# Openbook_Schematic.net
KiCad netlist of a schematic drawn in EAGLE
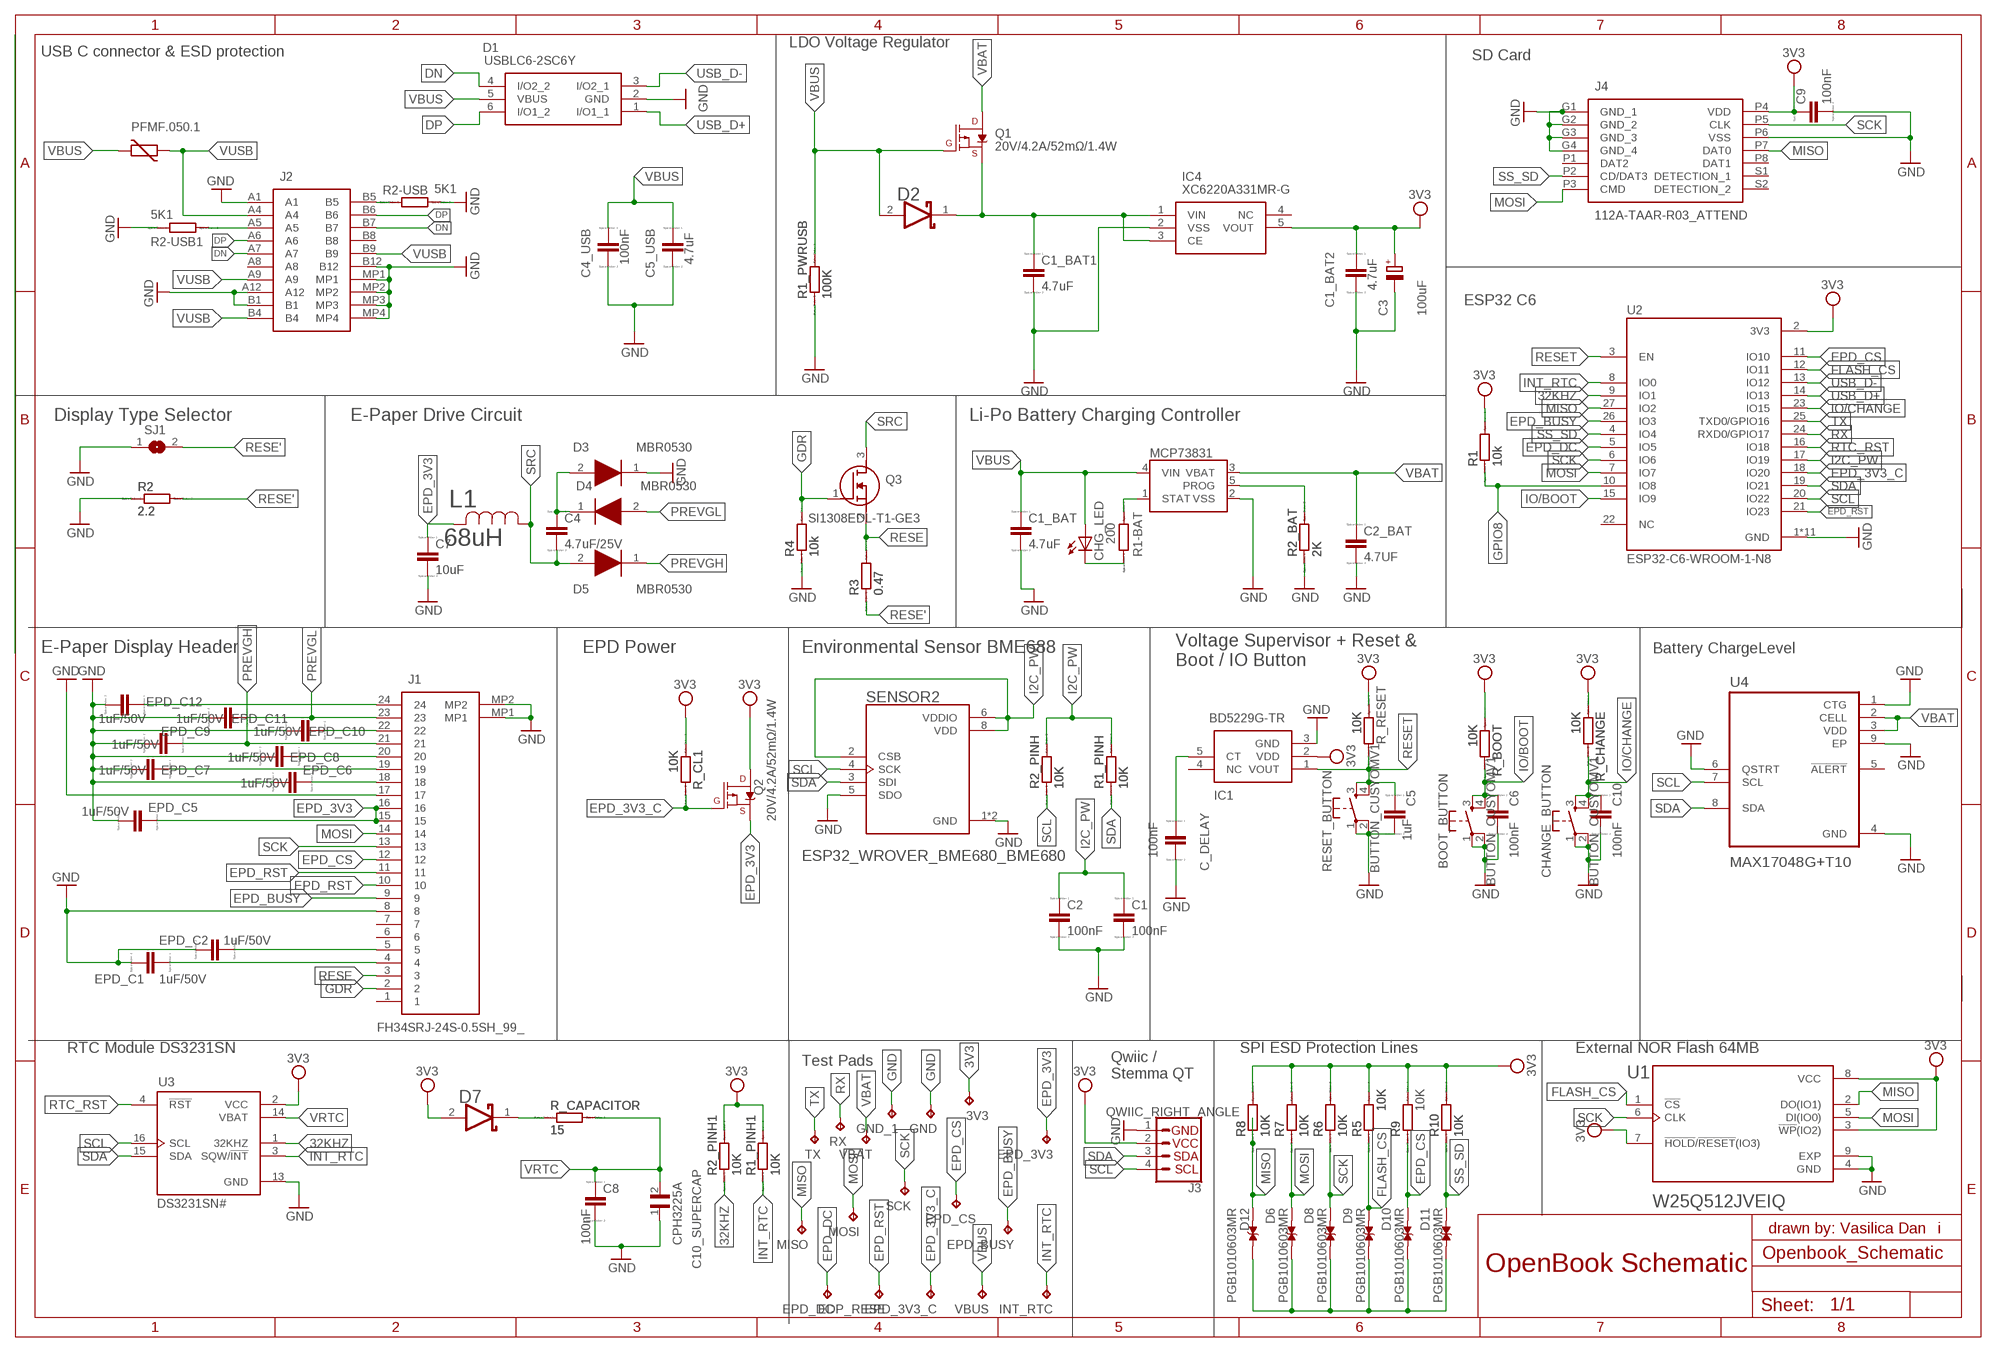
[diagram p0: schematic, sheet 1]

(export (version "E")
  (design (tool "Eeschema 10.0.6"))
  (components
    (comp (ref "3V3")
      (value "TPTP20R")
      (footprint "eagle-import:TP20R")
      (libsource (lib "eagle-import") (part "TPTP20R"))
    )
    (comp (ref "BOOT_BUTTON")
      (value "BUTTON_CUSYOMV1")
      (footprint "eagle-import:MYBUTTON")
      (libsource (lib "eagle-import") (part "BUTTON_CUSYOMV1"))
    )
    (comp (ref "C1")
      (value "100nF")
      (footprint "eagle-import:ESP32_WROVER_EAGLE-LTSPICE_C0402")
      (libsource (lib "eagle-import") (part "ESP32_WROVER_EAGLE-LTSPICE_CC0402"))
    )
    (comp (ref "C1_BAT")
      (value "4.7uF")
      (footprint "eagle-import:ESP32_WROVER_EAGLE-LTSPICE_C0402")
      (libsource (lib "eagle-import") (part "ESP32_WROVER_EAGLE-LTSPICE_CC0402"))
    )
    (comp (ref "C1_BAT1")
      (value "4.7uF")
      (footprint "eagle-import:ESP32_WROVER_EAGLE-LTSPICE_C0402")
      (libsource (lib "eagle-import") (part "ESP32_WROVER_EAGLE-LTSPICE_CC0402"))
    )
    (comp (ref "C1_BAT2")
      (value "4.7uF")
      (footprint "eagle-import:ESP32_WROVER_EAGLE-LTSPICE_C0402")
      (libsource (lib "eagle-import") (part "ESP32_WROVER_EAGLE-LTSPICE_CC0402"))
    )
    (comp (ref "C2")
      (value "100nF")
      (footprint "eagle-import:ESP32_WROVER_EAGLE-LTSPICE_C0402")
      (libsource (lib "eagle-import") (part "ESP32_WROVER_EAGLE-LTSPICE_CC0402"))
    )
    (comp (ref "C2_BAT")
      (value "4.7UF")
      (footprint "eagle-import:ESP32_WROVER_EAGLE-LTSPICE_C0402")
      (libsource (lib "eagle-import") (part "ESP32_WROVER_EAGLE-LTSPICE_CC0402"))
    )
    (comp (ref "C3")
      (value "100uF")
      (footprint "eagle-import:RCL_CT3528")
      (libsource (lib "eagle-import") (part "RCL_CPOL-EUCT3528"))
    )
    (comp (ref "C4")
      (value "4.7uF/25V")
      (footprint "eagle-import:ESP32_WROVER_EAGLE-LTSPICE_C0402")
      (libsource (lib "eagle-import") (part "ESP32_WROVER_EAGLE-LTSPICE_CC0402"))
    )
    (comp (ref "C4_USB")
      (value "100nF")
      (footprint "eagle-import:ESP32_WROVER_EAGLE-LTSPICE_C0402")
      (libsource (lib "eagle-import") (part "ESP32_WROVER_EAGLE-LTSPICE_CC0402"))
    )
    (comp (ref "C5")
      (value "1uF")
      (footprint "eagle-import:ESP32_WROVER_EAGLE-LTSPICE_C0402")
      (libsource (lib "eagle-import") (part "ESP32_WROVER_EAGLE-LTSPICE_CC0402"))
    )
    (comp (ref "C5_USB")
      (value "4.7uF")
      (footprint "eagle-import:ESP32_WROVER_EAGLE-LTSPICE_C0402")
      (libsource (lib "eagle-import") (part "ESP32_WROVER_EAGLE-LTSPICE_CC0402"))
    )
    (comp (ref "C6")
      (value "100nF")
      (footprint "eagle-import:ESP32_WROVER_EAGLE-LTSPICE_C0402")
      (libsource (lib "eagle-import") (part "ESP32_WROVER_EAGLE-LTSPICE_CC0402"))
    )
    (comp (ref "C7")
      (value "10uF")
      (footprint "eagle-import:ESP32_WROVER_EAGLE-LTSPICE_C0402")
      (libsource (lib "eagle-import") (part "ESP32_WROVER_EAGLE-LTSPICE_CC0402"))
    )
    (comp (ref "C8")
      (value "100nF")
      (footprint "eagle-import:ESP32_WROVER_EAGLE-LTSPICE_C0402")
      (libsource (lib "eagle-import") (part "ESP32_WROVER_EAGLE-LTSPICE_CC0402"))
    )
    (comp (ref "C9")
      (value "100nF")
      (footprint "eagle-import:ESP32_WROVER_EAGLE-LTSPICE_C0402")
      (libsource (lib "eagle-import") (part "ESP32_WROVER_EAGLE-LTSPICE_CC0402"))
    )
    (comp (ref "C10")
      (value "100nF")
      (footprint "eagle-import:ESP32_WROVER_EAGLE-LTSPICE_C0402")
      (libsource (lib "eagle-import") (part "ESP32_WROVER_EAGLE-LTSPICE_CC0402"))
    )
    (comp (ref "C10_SUPERCAP")
      (value "CPH3225A")
      (footprint "eagle-import:CAPCP3225X100N")
      (fields (field (name "MF") "Seiko Instruments"))
      (libsource (lib "eagle-import") (part "CPH3225A"))
    )
    (comp (ref "CHANGE_BUTTON")
      (value "BUTTON_CUSYOMV1")
      (footprint "eagle-import:MYBUTTON")
      (libsource (lib "eagle-import") (part "BUTTON_CUSYOMV1"))
    )
    (comp (ref "CHG_LED")
      (value "ADAFRUIT_LEDCHIP-LED0603")
      (footprint "eagle-import:ADAFRUIT_CHIP-LED0603")
      (libsource (lib "eagle-import") (part "ADAFRUIT_LEDCHIP-LED0603"))
    )
    (comp (ref "C_DELAY")
      (value "100nF")
      (footprint "eagle-import:ESP32_WROVER_EAGLE-LTSPICE_C0402")
      (libsource (lib "eagle-import") (part "ESP32_WROVER_EAGLE-LTSPICE_CC0402"))
    )
    (comp (ref "D1")
      (value "USBLC6-2SC6Y")
      (footprint "eagle-import:SOT95P280X145-6N")
      (fields (field (name "MF") "STMicroelectronics"))
      (libsource (lib "eagle-import") (part "USBLC6-2SC6Y"))
    )
    (comp (ref "D2")
      (value "ESP32_WROVER_AVX---SD0805S020S1R0_AVX_SD0805S020S1R0_0_0AVX_SD0805S020S1R0_0_0")
      (footprint "eagle-import:ESP32_WROVER_AVX---SD0805S020S1R0_AVX_SD0805S020S1R0_0")
      (fields
        (field (name "DIGIKEY_PART_NUMBER") "478-7800-1-ND")
        (field (name "MF") "AVX")
        (field (name "MOUSER_PART_NUMBER") "581-SD0805S020S1R0")
      )
      (libsource (lib "eagle-import") (part "ESP32_WROVER_AVX---SD0805S020S1R0_AVX_SD0805S020S1R0_0_0AVX_SD0805S020S1R0_0_0"))
    )
    (comp (ref "D3")
      (value "MBR0530")
      (footprint "eagle-import:SOD3716X135N")
      (fields (field (name "MF") "ON Semiconductor"))
      (libsource (lib "eagle-import") (part "MBR0530"))
    )
    (comp (ref "D4")
      (value "MBR0530")
      (footprint "eagle-import:SOD3716X135N")
      (fields (field (name "MF") "ON Semiconductor"))
      (libsource (lib "eagle-import") (part "MBR0530"))
    )
    (comp (ref "D5")
      (value "MBR0530")
      (footprint "eagle-import:SOD3716X135N")
      (fields (field (name "MF") "ON Semiconductor"))
      (libsource (lib "eagle-import") (part "MBR0530"))
    )
    (comp (ref "D6")
      (value "PGB1010603MR")
      (footprint "eagle-import:DIOC1608X36N")
      (fields (field (name "MF") "Littelfuse Inc."))
      (libsource (lib "eagle-import") (part "PGB1010603MR"))
    )
    (comp (ref "D7")
      (value "ESP32_WROVER_AVX---SD0805S020S1R0_AVX_SD0805S020S1R0_0_0AVX_SD0805S020S1R0_0_0")
      (footprint "eagle-import:ESP32_WROVER_AVX---SD0805S020S1R0_AVX_SD0805S020S1R0_0")
      (fields
        (field (name "DIGIKEY_PART_NUMBER") "478-7800-1-ND")
        (field (name "MF") "AVX")
        (field (name "MOUSER_PART_NUMBER") "581-SD0805S020S1R0")
      )
      (libsource (lib "eagle-import") (part "ESP32_WROVER_AVX---SD0805S020S1R0_AVX_SD0805S020S1R0_0_0AVX_SD0805S020S1R0_0_0"))
    )
    (comp (ref "D8")
      (value "PGB1010603MR")
      (footprint "eagle-import:DIOC1608X36N")
      (fields (field (name "MF") "Littelfuse Inc."))
      (libsource (lib "eagle-import") (part "PGB1010603MR"))
    )
    (comp (ref "D9")
      (value "PGB1010603MR")
      (footprint "eagle-import:DIOC1608X36N")
      (fields (field (name "MF") "Littelfuse Inc."))
      (libsource (lib "eagle-import") (part "PGB1010603MR"))
    )
    (comp (ref "D10")
      (value "PGB1010603MR")
      (footprint "eagle-import:DIOC1608X36N")
      (fields (field (name "MF") "Littelfuse Inc."))
      (libsource (lib "eagle-import") (part "PGB1010603MR"))
    )
    (comp (ref "D11")
      (value "PGB1010603MR")
      (footprint "eagle-import:DIOC1608X36N")
      (fields (field (name "MF") "Littelfuse Inc."))
      (libsource (lib "eagle-import") (part "PGB1010603MR"))
    )
    (comp (ref "D12")
      (value "PGB1010603MR")
      (footprint "eagle-import:DIOC1608X36N")
      (fields (field (name "MF") "Littelfuse Inc."))
      (libsource (lib "eagle-import") (part "PGB1010603MR"))
    )
    (comp (ref "EDP_RESE")
      (value "TPTP20R")
      (footprint "eagle-import:TP20R")
      (libsource (lib "eagle-import") (part "TPTP20R"))
    )
    (comp (ref "EPD_3V3")
      (value "TPTP20R")
      (footprint "eagle-import:TP20R")
      (libsource (lib "eagle-import") (part "TPTP20R"))
    )
    (comp (ref "EPD_3V3_C")
      (value "TPTP20R")
      (footprint "eagle-import:TP20R")
      (libsource (lib "eagle-import") (part "TPTP20R"))
    )
    (comp (ref "EPD_BUSY")
      (value "TPTP20R")
      (footprint "eagle-import:TP20R")
      (libsource (lib "eagle-import") (part "TPTP20R"))
    )
    (comp (ref "EPD_C1")
      (value "1uF/50V")
      (footprint "eagle-import:ESP32_WROVER_EAGLE-LTSPICE_C0402")
      (libsource (lib "eagle-import") (part "ESP32_WROVER_EAGLE-LTSPICE_CC0402"))
    )
    (comp (ref "EPD_C2")
      (value "1uF/50V")
      (footprint "eagle-import:ESP32_WROVER_EAGLE-LTSPICE_C0402")
      (libsource (lib "eagle-import") (part "ESP32_WROVER_EAGLE-LTSPICE_CC0402"))
    )
    (comp (ref "EPD_C5")
      (value "1uF/50V")
      (footprint "eagle-import:ESP32_WROVER_EAGLE-LTSPICE_C0402")
      (libsource (lib "eagle-import") (part "ESP32_WROVER_EAGLE-LTSPICE_CC0402"))
    )
    (comp (ref "EPD_C6")
      (value "1uF/50V")
      (footprint "eagle-import:ESP32_WROVER_EAGLE-LTSPICE_C0402")
      (libsource (lib "eagle-import") (part "ESP32_WROVER_EAGLE-LTSPICE_CC0402"))
    )
    (comp (ref "EPD_C7")
      (value "1uF/50V")
      (footprint "eagle-import:ESP32_WROVER_EAGLE-LTSPICE_C0402")
      (libsource (lib "eagle-import") (part "ESP32_WROVER_EAGLE-LTSPICE_CC0402"))
    )
    (comp (ref "EPD_C8")
      (value "1uF/50V")
      (footprint "eagle-import:ESP32_WROVER_EAGLE-LTSPICE_C0402")
      (libsource (lib "eagle-import") (part "ESP32_WROVER_EAGLE-LTSPICE_CC0402"))
    )
    (comp (ref "EPD_C9")
      (value "1uF/50V")
      (footprint "eagle-import:ESP32_WROVER_EAGLE-LTSPICE_C0402")
      (libsource (lib "eagle-import") (part "ESP32_WROVER_EAGLE-LTSPICE_CC0402"))
    )
    (comp (ref "EPD_C10")
      (value "1uF/50V")
      (footprint "eagle-import:ESP32_WROVER_EAGLE-LTSPICE_C0402")
      (libsource (lib "eagle-import") (part "ESP32_WROVER_EAGLE-LTSPICE_CC0402"))
    )
    (comp (ref "EPD_C11")
      (value "1uF/50V")
      (footprint "eagle-import:ESP32_WROVER_EAGLE-LTSPICE_C0402")
      (libsource (lib "eagle-import") (part "ESP32_WROVER_EAGLE-LTSPICE_CC0402"))
    )
    (comp (ref "EPD_C12")
      (value "1uF/50V")
      (footprint "eagle-import:ESP32_WROVER_EAGLE-LTSPICE_C0402")
      (libsource (lib "eagle-import") (part "ESP32_WROVER_EAGLE-LTSPICE_CC0402"))
    )
    (comp (ref "EPD_CS")
      (value "TPTP20R")
      (footprint "eagle-import:TP20R")
      (libsource (lib "eagle-import") (part "TPTP20R"))
    )
    (comp (ref "EPD_DC")
      (value "TPTP20R")
      (footprint "eagle-import:TP20R")
      (libsource (lib "eagle-import") (part "TPTP20R"))
    )
    (comp (ref "GND")
      (value "TPTP20R")
      (footprint "eagle-import:TP20R")
      (libsource (lib "eagle-import") (part "TPTP20R"))
    )
    (comp (ref "GND_1")
      (value "TPTP20R")
      (footprint "eagle-import:TP20R")
      (libsource (lib "eagle-import") (part "TPTP20R"))
    )
    (comp (ref "IC1")
      (value "BD5229G-TR")
      (footprint "eagle-import:SOT95P280X120-5N")
      (fields (field (name "MOUSER_PART_NUMBER") "755-BD5229G-TR"))
      (libsource (lib "eagle-import") (part "BD5229G-TR"))
    )
    (comp (ref "IC4")
      (value "XC6220A331MR-G")
      (footprint "eagle-import:SOT95P280X120-5N")
      (fields (field (name "MOUSER_PART_NUMBER") "865-XC6220A331MR-G"))
      (libsource (lib "eagle-import") (part "XC6220A331MR-G"))
    )
    (comp (ref "INT_RTC")
      (value "TPTP20R")
      (footprint "eagle-import:TP20R")
      (libsource (lib "eagle-import") (part "TPTP20R"))
    )
    (comp (ref "J1")
      (value "FH34SRJ-24S-0.5SH_99_")
      (footprint "eagle-import:FH34SRJ24S05SH99")
      (fields
        (field (name "MANUFACTURER_PART_NUMBER") "FH34SRJ-24S-0.5SH(99)")
        (field (name "MOUSER_PART_NUMBER") "798-FH34SRJ24S05SH99")
      )
      (libsource (lib "eagle-import") (part "FH34SRJ-24S-0.5SH_99_"))
    )
    (comp (ref "J2")
      (value "SAMACSYS_PARTS_USB4110-GF-A")
      (footprint "eagle-import:SAMACSYS_PARTS_USB4110GFA")
      (fields
        (field (name "MANUFACTURER_PART_NUMBER") "USB4110-GF-A")
        (field (name "MOUSER_PART_NUMBER") "640-USB4110-GF-A")
      )
      (libsource (lib "eagle-import") (part "SAMACSYS_PARTS_USB4110-GF-A"))
    )
    (comp (ref "J3")
      (value "QWIIC_RIGHT_ANGLE")
      (footprint "eagle-import:JST04_1MM_RA")
      (libsource (lib "eagle-import") (part "QWIIC_CONNECTORJS-1MM"))
    )
    (comp (ref "J4")
      (value "112A-TAAR-R03_ATTEND")
      (footprint "eagle-import:112ATAARR03ATTEND")
      (fields (field (name "MANUFACTURER_PART_NUMBER") "112A-TAAR-R03 ATTEND"))
      (libsource (lib "eagle-import") (part "112A-TAAR-R03_ATTEND"))
    )
    (comp (ref "L1")
      (value "68uH")
      (footprint "eagle-import:IND_4828-WE-TPC_WRE")
      (fields
        (field (name "MANUFACTURER_PART_NUMBER") "744043680")
        (field (name "COPYRIGHT") "Copyright (C) 2024 Ultra Librarian. All rights reserved.")
      )
      (libsource (lib "eagle-import") (part "744043680IND_4828-WE-TPC_WRE"))
    )
    (comp (ref "MCP73831")
      (value "ESP32_WROVER_SPARKFUN-IC-POWER_MCP73831")
      (footprint "eagle-import:ESP32_WROVER_SPARKFUN-IC-POWER_SOT23-5")
      (libsource (lib "eagle-import") (part "ESP32_WROVER_SPARKFUN-IC-POWER_MCP73831"))
    )
    (comp (ref "MISO")
      (value "TPTP20R")
      (footprint "eagle-import:TP20R")
      (libsource (lib "eagle-import") (part "TPTP20R"))
    )
    (comp (ref "MOSI")
      (value "TPTP20R")
      (footprint "eagle-import:TP20R")
      (libsource (lib "eagle-import") (part "TPTP20R"))
    )
    (comp (ref "PFMF.050.1")
      (value "ESP32C6_VARISTORCN1812")
      (footprint "eagle-import:ESP32C6_VARISTOR_CT_CN1812")
      (libsource (lib "eagle-import") (part "ESP32C6_VARISTORCN1812"))
    )
    (comp (ref "Q1")
      (value "20V/4.2A/52mΩ/1.4W")
      (footprint "eagle-import:ESP32_WROVER_SPARKFUN-DISCRETESEMI_SOT23-3")
      (libsource (lib "eagle-import") (part "ESP32_WROVER_SPARKFUN-DISCRETESEMI_MOSFET_PCH-DMG2305UX-7"))
    )
    (comp (ref "Q2")
      (value "20V/4.2A/52mΩ/1.4W")
      (footprint "eagle-import:ESP32_WROVER_SPARKFUN-DISCRETESEMI_SOT23-3")
      (libsource (lib "eagle-import") (part "ESP32_WROVER_SPARKFUN-DISCRETESEMI_MOSFET_PCH-DMG2305UX-7"))
    )
    (comp (ref "Q3")
      (value "SI1308EDL-T1-GE3")
      (footprint "eagle-import:SOT65P210X110-3N")
      (fields (field (name "MF") "Vishay Siliconix"))
      (libsource (lib "eagle-import") (part "SI1308EDL-T1-GE3"))
    )
    (comp (ref "R1")
      (value "10k")
      (footprint "eagle-import:ESP32_WROVER_EAGLE-LTSPICE_R0402")
      (libsource (lib "eagle-import") (part "ESP32_WROVER_EAGLE-LTSPICE_RR0402"))
    )
    (comp (ref "R1-BAT")
      (value "200")
      (footprint "eagle-import:ESP32_WROVER_EAGLE-LTSPICE_R0402")
      (libsource (lib "eagle-import") (part "ESP32_WROVER_EAGLE-LTSPICE_RR0402"))
    )
    (comp (ref "R1_PINH")
      (value "10K")
      (footprint "eagle-import:ESP32_WROVER_EAGLE-LTSPICE_R0402")
      (libsource (lib "eagle-import") (part "ESP32_WROVER_EAGLE-LTSPICE_RR0402"))
    )
    (comp (ref "R1_PINH1")
      (value "10K")
      (footprint "eagle-import:ESP32_WROVER_EAGLE-LTSPICE_R0402")
      (libsource (lib "eagle-import") (part "ESP32_WROVER_EAGLE-LTSPICE_RR0402"))
    )
    (comp (ref "R1_PWRUSB")
      (value "100K")
      (footprint "eagle-import:ESP32_WROVER_EAGLE-LTSPICE_R0402")
      (libsource (lib "eagle-import") (part "ESP32_WROVER_EAGLE-LTSPICE_RR0402"))
    )
    (comp (ref "R2")
      (value "2.2")
      (footprint "eagle-import:ESP32_WROVER_EAGLE-LTSPICE_R0402")
      (libsource (lib "eagle-import") (part "ESP32_WROVER_EAGLE-LTSPICE_RR0402"))
    )
    (comp (ref "R2-USB")
      (value "5K1")
      (footprint "eagle-import:ESP32_WROVER_EAGLE-LTSPICE_R0402")
      (libsource (lib "eagle-import") (part "ESP32_WROVER_EAGLE-LTSPICE_RR0402"))
    )
    (comp (ref "R2-USB1")
      (value "5K1")
      (footprint "eagle-import:ESP32_WROVER_EAGLE-LTSPICE_R0402")
      (libsource (lib "eagle-import") (part "ESP32_WROVER_EAGLE-LTSPICE_RR0402"))
    )
    (comp (ref "R2_BAT")
      (value "2K")
      (footprint "eagle-import:ESP32_WROVER_EAGLE-LTSPICE_R0402")
      (libsource (lib "eagle-import") (part "ESP32_WROVER_EAGLE-LTSPICE_RR0402"))
    )
    (comp (ref "R2_PINH")
      (value "10K")
      (footprint "eagle-import:ESP32_WROVER_EAGLE-LTSPICE_R0402")
      (libsource (lib "eagle-import") (part "ESP32_WROVER_EAGLE-LTSPICE_RR0402"))
    )
    (comp (ref "R2_PINH1")
      (value "10K")
      (footprint "eagle-import:ESP32_WROVER_EAGLE-LTSPICE_R0402")
      (libsource (lib "eagle-import") (part "ESP32_WROVER_EAGLE-LTSPICE_RR0402"))
    )
    (comp (ref "R3")
      (value "0.47")
      (footprint "eagle-import:ESP32_WROVER_EAGLE-LTSPICE_R0402")
      (libsource (lib "eagle-import") (part "ESP32_WROVER_EAGLE-LTSPICE_RR0402"))
    )
    (comp (ref "R4")
      (value "10k")
      (footprint "eagle-import:ESP32_WROVER_EAGLE-LTSPICE_R0402")
      (libsource (lib "eagle-import") (part "ESP32_WROVER_EAGLE-LTSPICE_RR0402"))
    )
    (comp (ref "R5")
      (value "10K")
      (footprint "eagle-import:ESP32_WROVER_EAGLE-LTSPICE_R0402")
      (libsource (lib "eagle-import") (part "ESP32_WROVER_EAGLE-LTSPICE_RR0402"))
    )
    (comp (ref "R6")
      (value "10K")
      (footprint "eagle-import:ESP32_WROVER_EAGLE-LTSPICE_R0402")
      (libsource (lib "eagle-import") (part "ESP32_WROVER_EAGLE-LTSPICE_RR0402"))
    )
    (comp (ref "R7")
      (value "10K")
      (footprint "eagle-import:ESP32_WROVER_EAGLE-LTSPICE_R0402")
      (libsource (lib "eagle-import") (part "ESP32_WROVER_EAGLE-LTSPICE_RR0402"))
    )
    (comp (ref "R8")
      (value "10K")
      (footprint "eagle-import:ESP32_WROVER_EAGLE-LTSPICE_R0402")
      (libsource (lib "eagle-import") (part "ESP32_WROVER_EAGLE-LTSPICE_RR0402"))
    )
    (comp (ref "R9")
      (value "10K")
      (footprint "eagle-import:ESP32_WROVER_EAGLE-LTSPICE_R0402")
      (libsource (lib "eagle-import") (part "ESP32_WROVER_EAGLE-LTSPICE_RR0402"))
    )
    (comp (ref "R10")
      (value "10K")
      (footprint "eagle-import:ESP32_WROVER_EAGLE-LTSPICE_R0402")
      (libsource (lib "eagle-import") (part "ESP32_WROVER_EAGLE-LTSPICE_RR0402"))
    )
    (comp (ref "RESET_BUTTON")
      (value "BUTTON_CUSYOMV1")
      (footprint "eagle-import:MYBUTTON")
      (libsource (lib "eagle-import") (part "BUTTON_CUSYOMV1"))
    )
    (comp (ref "RX")
      (value "TPTP20R")
      (footprint "eagle-import:TP20R")
      (libsource (lib "eagle-import") (part "TPTP20R"))
    )
    (comp (ref "R_BOOT")
      (value "10K")
      (footprint "eagle-import:ESP32_WROVER_EAGLE-LTSPICE_R0402")
      (libsource (lib "eagle-import") (part "ESP32_WROVER_EAGLE-LTSPICE_RR0402"))
    )
    (comp (ref "R_CAPACITOR")
      (value "15")
      (footprint "eagle-import:ESP32_WROVER_EAGLE-LTSPICE_R0402")
      (libsource (lib "eagle-import") (part "ESP32_WROVER_EAGLE-LTSPICE_RR0402"))
    )
    (comp (ref "R_CHANGE")
      (value "10K")
      (footprint "eagle-import:ESP32_WROVER_EAGLE-LTSPICE_R0402")
      (libsource (lib "eagle-import") (part "ESP32_WROVER_EAGLE-LTSPICE_RR0402"))
    )
    (comp (ref "R_CL1")
      (value "10K")
      (footprint "eagle-import:ESP32_WROVER_EAGLE-LTSPICE_R0402")
      (libsource (lib "eagle-import") (part "ESP32_WROVER_EAGLE-LTSPICE_RR0402"))
    )
    (comp (ref "R_RESET")
      (value "10K")
      (footprint "eagle-import:ESP32_WROVER_EAGLE-LTSPICE_R0402")
      (libsource (lib "eagle-import") (part "ESP32_WROVER_EAGLE-LTSPICE_RR0402"))
    )
    (comp (ref "SCK")
      (value "TPTP20R")
      (footprint "eagle-import:TP20R")
      (libsource (lib "eagle-import") (part "TPTP20R"))
    )
    (comp (ref "SENSOR2")
      (value "ESP32_WROVER_BME680_BME680")
      (footprint "eagle-import:ESP32_WROVER_BME680_PSON80P300X300X100-8N")
      (fields (field (name "MF") "Bosch Sensortec") (field (name "MP") "BME680"))
      (libsource (lib "eagle-import") (part "ESP32_WROVER_BME680_BME680"))
    )
    (comp (ref "SJ1") (value "SJ") (footprint "eagle-import:SJ") (libsource (lib "eagle-import") (part "SJ")))
    (comp (ref "TX")
      (value "TPTP20R")
      (footprint "eagle-import:TP20R")
      (libsource (lib "eagle-import") (part "TPTP20R"))
    )
    (comp (ref "U1")
      (value "W25Q512JVEIQ")
      (footprint "eagle-import:SON127P600X800X80-9N")
      (fields (field (name "MF") "Winbond Electronics"))
      (libsource (lib "eagle-import") (part "W25Q512JVEIQ"))
    )
    (comp (ref "U2")
      (value "ESP32-C6-WROOM-1-N8")
      (footprint "eagle-import:XCVR_ESP32-C6-WROOM-1-N8")
      (fields (field (name "MF") "Espressif Systems"))
      (libsource (lib "eagle-import") (part "ESP32-C6-WROOM-1-N8"))
    )
    (comp (ref "U3")
      (value "DS3231SN#")
      (footprint "eagle-import:SOIC127P1032X265-16N")
      (fields (field (name "MF") "Analog Devices"))
      (libsource (lib "eagle-import") (part "DS3231SN#"))
    )
    (comp (ref "U4")
      (value "MAX17048G+T10")
      (footprint "eagle-import:SON50P200X200X80-9N")
      (fields (field (name "MF") "Analog Devices"))
      (libsource (lib "eagle-import") (part "MAX17048G+T10"))
    )
    (comp (ref "VBAT")
      (value "TPTP20R")
      (footprint "eagle-import:TP20R")
      (libsource (lib "eagle-import") (part "TPTP20R"))
    )
    (comp (ref "VBUS")
      (value "TPTP20R")
      (footprint "eagle-import:TP20R")
      (libsource (lib "eagle-import") (part "TPTP20R"))
    )
  )
  (nets
    (net (code "1") (name "3V3") (class "Default")
      (node (ref "3V3") (pin "TP") (pinfunction "TP_TP") (pintype "input"))
      (node (ref "C1_BAT2") (pin "1") (pinfunction "1_1") (pintype "passive"))
      (node (ref "C3") (pin "+") (pinfunction "+_+") (pintype "passive"))
      (node (ref "C9") (pin "1") (pinfunction "1_1") (pintype "passive"))
      (node (ref "D7") (pin "2") (pinfunction "ANODE_2") (pintype "bidirectional"))
      (node (ref "IC1") (pin "2") (pinfunction "VDD_2") (pintype "bidirectional"))
      (node (ref "IC4") (pin "5") (pinfunction "VOUT_5") (pintype "bidirectional"))
      (node (ref "J3") (pin "2") (pinfunction "2_2") (pintype "power_in"))
      (node (ref "J4") (pin "P4") (pinfunction "VDD_P4") (pintype "bidirectional"))
      (node (ref "Q2") (pin "3") (pinfunction "D_3") (pintype "bidirectional"))
      (node (ref "R1") (pin "2") (pinfunction "2_2") (pintype "passive"))
      (node (ref "R10") (pin "2") (pinfunction "2_2") (pintype "passive"))
      (node (ref "R1_PINH1") (pin "2") (pinfunction "2_2") (pintype "passive"))
      (node (ref "R2_PINH1") (pin "2") (pinfunction "2_2") (pintype "passive"))
      (node (ref "R5") (pin "2") (pinfunction "2_2") (pintype "passive"))
      (node (ref "R6") (pin "2") (pinfunction "2_2") (pintype "passive"))
      (node (ref "R7") (pin "2") (pinfunction "2_2") (pintype "passive"))
      (node (ref "R8") (pin "2") (pinfunction "2_2") (pintype "passive"))
      (node (ref "R9") (pin "2") (pinfunction "2_2") (pintype "passive"))
      (node (ref "R_BOOT") (pin "1") (pinfunction "1_1") (pintype "passive"))
      (node (ref "R_CHANGE") (pin "1") (pinfunction "1_1") (pintype "passive"))
      (node (ref "R_CL1") (pin "1") (pinfunction "1_1") (pintype "passive"))
      (node (ref "R_RESET") (pin "1") (pinfunction "1_1") (pintype "passive"))
      (node (ref "U1") (pin "3") (pinfunction "~{WP}(IO2)_3") (pintype "bidirectional"))
      (node (ref "U1") (pin "7") (pinfunction "~{HOLD}/~{RESET}(IO3)_7") (pintype "bidirectional"))
      (node (ref "U1") (pin "8") (pinfunction "VCC_8") (pintype "power_in"))
      (node (ref "U2") (pin "2") (pinfunction "3V3_2") (pintype "power_in"))
      (node (ref "U3") (pin "2") (pinfunction "VCC_2") (pintype "power_in"))
    )
    (net (code "2") (name "32KHZ") (class "Default")
      (node (ref "R2_PINH1") (pin "1") (pinfunction "1_1") (pintype "passive"))
      (node (ref "U2") (pin "9") (pinfunction "IO1_9") (pintype "bidirectional"))
      (node (ref "U3") (pin "1") (pinfunction "32KHZ_1") (pintype "output"))
    )
    (net (code "3") (name "DN") (class "Default")
      (node (ref "D1") (pin "4") (pinfunction "I/O2_2_4") (pintype "bidirectional"))
      (node (ref "J2") (pin "A7") (pinfunction "A7_A7") (pintype "bidirectional"))
      (node (ref "J2") (pin "B7") (pinfunction "B7_B7") (pintype "bidirectional"))
    )
    (net (code "4") (name "DP") (class "Default")
      (node (ref "D1") (pin "6") (pinfunction "I/O1_2_6") (pintype "bidirectional"))
      (node (ref "J2") (pin "A6") (pinfunction "A6_A6") (pintype "bidirectional"))
      (node (ref "J2") (pin "B6") (pinfunction "B6_B6") (pintype "bidirectional"))
    )
    (net (code "5") (name "EPD_3V3") (class "Default")
      (node (ref "C7") (pin "1") (pinfunction "1_1") (pintype "passive"))
      (node (ref "EPD_3V3") (pin "TP") (pinfunction "TP_TP") (pintype "input"))
      (node (ref "EPD_C5") (pin "1") (pinfunction "1_1") (pintype "passive"))
      (node (ref "J1") (pin "15") (pinfunction "15_15") (pintype "bidirectional"))
      (node (ref "J1") (pin "16") (pinfunction "16_16") (pintype "bidirectional"))
      (node (ref "L1") (pin "2") (pinfunction "2_2") (pintype "passive"))
      (node (ref "Q2") (pin "2") (pinfunction "S_2") (pintype "bidirectional"))
    )
    (net (code "6") (name "EPD_3V3_C") (class "Default")
      (node (ref "EPD_3V3_C") (pin "TP") (pinfunction "TP_TP") (pintype "input"))
      (node (ref "Q2") (pin "1") (pinfunction "G_1") (pintype "bidirectional"))
      (node (ref "R_CL1") (pin "2") (pinfunction "2_2") (pintype "passive"))
      (node (ref "U2") (pin "18") (pinfunction "IO20_18") (pintype "bidirectional"))
    )
    (net (code "7") (name "EPD_BUSY") (class "Default")
      (node (ref "EPD_BUSY") (pin "TP") (pinfunction "TP_TP") (pintype "input"))
      (node (ref "J1") (pin "9") (pinfunction "9_9") (pintype "bidirectional"))
      (node (ref "U2") (pin "26") (pinfunction "IO3_26") (pintype "bidirectional"))
    )
    (net (code "8") (name "EPD_CS") (class "Default")
      (node (ref "D10") (pin "1") (pinfunction "1_1") (pintype "passive"))
      (node (ref "EPD_CS") (pin "TP") (pinfunction "TP_TP") (pintype "input"))
      (node (ref "J1") (pin "12") (pinfunction "12_12") (pintype "bidirectional"))
      (node (ref "R9") (pin "1") (pinfunction "1_1") (pintype "passive"))
      (node (ref "U2") (pin "11") (pinfunction "IO10_11") (pintype "bidirectional"))
    )
    (net (code "9") (name "EPD_DC") (class "Default")
      (node (ref "EPD_DC") (pin "TP") (pinfunction "TP_TP") (pintype "input"))
      (node (ref "U2") (pin "5") (pinfunction "IO5_5") (pintype "bidirectional"))
    )
    (net (code "10") (name "EPD_RST") (class "Default")
      (node (ref "EDP_RESE") (pin "TP") (pinfunction "TP_TP") (pintype "input"))
      (node (ref "J1") (pin "10") (pinfunction "10_10") (pintype "bidirectional"))
      (node (ref "J1") (pin "11") (pinfunction "11_11") (pintype "bidirectional"))
      (node (ref "U2") (pin "21") (pinfunction "IO23_21") (pintype "bidirectional"))
    )
    (net (code "11") (name "FLASH_CS") (class "Default")
      (node (ref "D9") (pin "1") (pinfunction "1_1") (pintype "passive"))
      (node (ref "R5") (pin "1") (pinfunction "1_1") (pintype "passive"))
      (node (ref "U1") (pin "1") (pinfunction "~{CS}_1") (pintype "input"))
      (node (ref "U2") (pin "12") (pinfunction "IO11_12") (pintype "bidirectional"))
    )
    (net (code "12") (name "GDR") (class "Default")
      (node (ref "J1") (pin "2") (pinfunction "2_2") (pintype "bidirectional"))
      (node (ref "Q3") (pin "1") (pinfunction "G_1") (pintype "bidirectional"))
      (node (ref "R4") (pin "2") (pinfunction "2_2") (pintype "passive"))
    )
    (net (code "13") (name "GND") (class "Default")
      (node (ref "BOOT_BUTTON") (pin "1") (pinfunction "1_1") (pintype "passive"))
      (node (ref "BOOT_BUTTON") (pin "2") (pinfunction "2_2") (pintype "passive"))
      (node (ref "C1") (pin "2") (pinfunction "2_2") (pintype "passive"))
      (node (ref "C10") (pin "2") (pinfunction "2_2") (pintype "passive"))
      (node (ref "C10_SUPERCAP") (pin "1") (pinfunction "1_1") (pintype "passive"))
      (node (ref "C1_BAT") (pin "2") (pinfunction "2_2") (pintype "passive"))
      (node (ref "C1_BAT1") (pin "2") (pinfunction "2_2") (pintype "passive"))
      (node (ref "C1_BAT2") (pin "2") (pinfunction "2_2") (pintype "passive"))
      (node (ref "C2") (pin "2") (pinfunction "2_2") (pintype "passive"))
      (node (ref "C2_BAT") (pin "2") (pinfunction "2_2") (pintype "passive"))
      (node (ref "C3") (pin "-") (pinfunction "-_-") (pintype "passive"))
      (node (ref "C4_USB") (pin "2") (pinfunction "2_2") (pintype "passive"))
      (node (ref "C5") (pin "2") (pinfunction "2_2") (pintype "passive"))
      (node (ref "C5_USB") (pin "2") (pinfunction "2_2") (pintype "passive"))
      (node (ref "C6") (pin "2") (pinfunction "2_2") (pintype "passive"))
      (node (ref "C7") (pin "2") (pinfunction "2_2") (pintype "passive"))
      (node (ref "C8") (pin "2") (pinfunction "2_2") (pintype "passive"))
      (node (ref "C9") (pin "2") (pinfunction "2_2") (pintype "passive"))
      (node (ref "CHANGE_BUTTON") (pin "1") (pinfunction "1_1") (pintype "passive"))
      (node (ref "CHANGE_BUTTON") (pin "2") (pinfunction "2_2") (pintype "passive"))
      (node (ref "C_DELAY") (pin "2") (pinfunction "2_2") (pintype "passive"))
      (node (ref "D1") (pin "2") (pinfunction "GND_2") (pintype "bidirectional"))
      (node (ref "D3") (pin "1") (pinfunction "K_1") (pintype "bidirectional"))
      (node (ref "EPD_C1") (pin "2") (pinfunction "2_2") (pintype "passive"))
      (node (ref "EPD_C10") (pin "2") (pinfunction "2_2") (pintype "passive"))
      (node (ref "EPD_C11") (pin "2") (pinfunction "2_2") (pintype "passive"))
      (node (ref "EPD_C12") (pin "2") (pinfunction "2_2") (pintype "passive"))
      (node (ref "EPD_C2") (pin "2") (pinfunction "2_2") (pintype "passive"))
      (node (ref "EPD_C5") (pin "2") (pinfunction "2_2") (pintype "passive"))
      (node (ref "EPD_C6") (pin "2") (pinfunction "2_2") (pintype "passive"))
      (node (ref "EPD_C7") (pin "2") (pinfunction "2_2") (pintype "passive"))
      (node (ref "EPD_C8") (pin "2") (pinfunction "2_2") (pintype "passive"))
      (node (ref "EPD_C9") (pin "2") (pinfunction "2_2") (pintype "passive"))
      (node (ref "GND") (pin "TP") (pinfunction "TP_TP") (pintype "input"))
      (node (ref "GND_1") (pin "TP") (pinfunction "TP_TP") (pintype "input"))
      (node (ref "IC1") (pin "3") (pinfunction "GND_3") (pintype "bidirectional"))
      (node (ref "IC4") (pin "2") (pinfunction "VSS_2") (pintype "bidirectional"))
      (node (ref "J1") (pin "17") (pinfunction "17_17") (pintype "bidirectional"))
      (node (ref "J1") (pin "8") (pinfunction "8_8") (pintype "bidirectional"))
      (node (ref "J1") (pin "MP1") (pinfunction "MP1_MP1") (pintype "bidirectional"))
      (node (ref "J1") (pin "MP2") (pinfunction "MP2_MP2") (pintype "bidirectional"))
      (node (ref "J2") (pin "A1") (pinfunction "A1_A1") (pintype "bidirectional"))
      (node (ref "J2") (pin "A12") (pinfunction "A12_A12") (pintype "bidirectional"))
      (node (ref "J2") (pin "B1") (pinfunction "B1_B1") (pintype "bidirectional"))
      (node (ref "J2") (pin "B12") (pinfunction "B12_B12") (pintype "bidirectional"))
      (node (ref "J2") (pin "MP1") (pinfunction "MP1_MP1") (pintype "bidirectional"))
      (node (ref "J2") (pin "MP2") (pinfunction "MP2_MP2") (pintype "bidirectional"))
      (node (ref "J2") (pin "MP3") (pinfunction "MP3_MP3") (pintype "bidirectional"))
      (node (ref "J2") (pin "MP4") (pinfunction "MP4_MP4") (pintype "bidirectional"))
      (node (ref "J3") (pin "1") (pinfunction "1_1") (pintype "power_in"))
      (node (ref "J4") (pin "G1") (pinfunction "GND_1_G1") (pintype "bidirectional"))
      (node (ref "J4") (pin "G2") (pinfunction "GND_2_G2") (pintype "bidirectional"))
      (node (ref "J4") (pin "G3") (pinfunction "GND_3_G3") (pintype "bidirectional"))
      (node (ref "J4") (pin "G4") (pinfunction "GND_4_G4") (pintype "bidirectional"))
      (node (ref "J4") (pin "P6") (pinfunction "VSS_P6") (pintype "bidirectional"))
      (node (ref "MCP73831") (pin "2") (pinfunction "VSS_2") (pintype "power_in"))
      (node (ref "R1_PWRUSB") (pin "1") (pinfunction "1_1") (pintype "passive"))
      (node (ref "R2") (pin "1") (pinfunction "1_1") (pintype "passive"))
      (node (ref "R2-USB") (pin "2") (pinfunction "2_2") (pintype "passive"))
      (node (ref "R2-USB1") (pin "1") (pinfunction "1_1") (pintype "passive"))
      (node (ref "R2_BAT") (pin "1") (pinfunction "1_1") (pintype "passive"))
      (node (ref "R4") (pin "1") (pinfunction "1_1") (pintype "passive"))
      (node (ref "RESET_BUTTON") (pin "1") (pinfunction "1_1") (pintype "passive"))
      (node (ref "RESET_BUTTON") (pin "2") (pinfunction "2_2") (pintype "passive"))
      (node (ref "SENSOR2") (pin "1") (pinfunction "GND_1") (pintype "power_in"))
      (node (ref "SENSOR2") (pin "5") (pinfunction "SDO_5") (pintype "bidirectional"))
      (node (ref "SENSOR2") (pin "7") (pinfunction "GND_7") (pintype "power_in"))
      (node (ref "SJ1") (pin "1") (pinfunction "1_1") (pintype "passive"))
      (node (ref "U1") (pin "4") (pinfunction "GND_4") (pintype "power_in"))
      (node (ref "U1") (pin "9") (pinfunction "EXP_9") (pintype "passive"))
      (node (ref "U2") (pin "1") (pinfunction "GND_1") (pintype "power_in"))
      (node (ref "U2") (pin "28") (pinfunction "GND_28") (pintype "power_in"))
      (node (ref "U2") (pin "29_1") (pinfunction "GND_29_1") (pintype "power_in"))
      (node (ref "U2") (pin "29_2") (pinfunction "GND_29_2") (pintype "power_in"))
      (node (ref "U2") (pin "29_3") (pinfunction "GND_29_3") (pintype "power_in"))
      (node (ref "U2") (pin "29_4") (pinfunction "GND_29_4") (pintype "power_in"))
      (node (ref "U2") (pin "29_5") (pinfunction "GND_29_5") (pintype "power_in"))
      (node (ref "U2") (pin "29_6") (pinfunction "GND_29_6") (pintype "power_in"))
      (node (ref "U2") (pin "29_7") (pinfunction "GND_29_7") (pintype "power_in"))
      (node (ref "U2") (pin "29_8") (pinfunction "GND_29_8") (pintype "power_in"))
      (node (ref "U2") (pin "29_9") (pinfunction "GND_29_9") (pintype "power_in"))
      (node (ref "U3") (pin "13") (pinfunction "GND_13") (pintype "power_in"))
      (node (ref "U4") (pin "1") (pinfunction "CTG_1") (pintype "power_in"))
      (node (ref "U4") (pin "4") (pinfunction "GND_4") (pintype "power_in"))
      (node (ref "U4") (pin "6") (pinfunction "QSTRT_6") (pintype "input"))
      (node (ref "U4") (pin "9") (pinfunction "EP_9") (pintype "power_in"))
    )
    (net (code "14") (name "GPIO8") (class "Default")
      (node (ref "R1") (pin "1") (pinfunction "1_1") (pintype "passive"))
      (node (ref "U2") (pin "10") (pinfunction "IO8_10") (pintype "bidirectional"))
    )
    (net (code "15") (name "I2C_PW") (class "Default")
      (node (ref "C1") (pin "1") (pinfunction "1_1") (pintype "passive"))
      (node (ref "C2") (pin "1") (pinfunction "1_1") (pintype "passive"))
      (node (ref "R1_PINH") (pin "2") (pinfunction "2_2") (pintype "passive"))
      (node (ref "R2_PINH") (pin "2") (pinfunction "2_2") (pintype "passive"))
      (node (ref "SENSOR2") (pin "2") (pinfunction "CSB_2") (pintype "input"))
      (node (ref "SENSOR2") (pin "6") (pinfunction "VDDIO_6") (pintype "power_in"))
      (node (ref "SENSOR2") (pin "8") (pinfunction "VDD_8") (pintype "power_in"))
      (node (ref "U2") (pin "17") (pinfunction "IO19_17") (pintype "bidirectional"))
    )
    (net (code "16") (name "INT_RTC") (class "Default")
      (node (ref "INT_RTC") (pin "TP") (pinfunction "TP_TP") (pintype "input"))
      (node (ref "R1_PINH1") (pin "1") (pinfunction "1_1") (pintype "passive"))
      (node (ref "U2") (pin "8") (pinfunction "IO0_8") (pintype "bidirectional"))
      (node (ref "U3") (pin "3") (pinfunction "SQW/~{INT}_3") (pintype "output"))
    )
    (net (code "17") (name "IO{slash}BOOT") (class "Default")
      (node (ref "BOOT_BUTTON") (pin "3") (pinfunction "3_3") (pintype "passive"))
      (node (ref "BOOT_BUTTON") (pin "4") (pinfunction "4_4") (pintype "passive"))
      (node (ref "C6") (pin "1") (pinfunction "1_1") (pintype "passive"))
      (node (ref "R_BOOT") (pin "2") (pinfunction "2_2") (pintype "passive"))
      (node (ref "U2") (pin "15") (pinfunction "IO9_15") (pintype "bidirectional"))
    )
    (net (code "18") (name "IO{slash}CHANGE") (class "Default")
      (node (ref "C10") (pin "1") (pinfunction "1_1") (pintype "passive"))
      (node (ref "CHANGE_BUTTON") (pin "3") (pinfunction "3_3") (pintype "passive"))
      (node (ref "CHANGE_BUTTON") (pin "4") (pinfunction "4_4") (pintype "passive"))
      (node (ref "R_CHANGE") (pin "2") (pinfunction "2_2") (pintype "passive"))
      (node (ref "U2") (pin "23") (pinfunction "IO15_23") (pintype "bidirectional"))
    )
    (net (code "19") (name "MISO") (class "Default")
      (node (ref "D12") (pin "1") (pinfunction "1_1") (pintype "passive"))
      (node (ref "J4") (pin "P7") (pinfunction "DAT0_P7") (pintype "bidirectional"))
      (node (ref "MISO") (pin "TP") (pinfunction "TP_TP") (pintype "input"))
      (node (ref "R8") (pin "1") (pinfunction "1_1") (pintype "passive"))
      (node (ref "U1") (pin "2") (pinfunction "DO(IO1)_2") (pintype "bidirectional"))
      (node (ref "U2") (pin "27") (pinfunction "IO2_27") (pintype "bidirectional"))
    )
    (net (code "20") (name "MOSI") (class "Default")
      (node (ref "D6") (pin "1") (pinfunction "1_1") (pintype "passive"))
      (node (ref "J1") (pin "14") (pinfunction "14_14") (pintype "bidirectional"))
      (node (ref "J4") (pin "P3") (pinfunction "CMD_P3") (pintype "bidirectional"))
      (node (ref "MOSI") (pin "TP") (pinfunction "TP_TP") (pintype "input"))
      (node (ref "R7") (pin "1") (pinfunction "1_1") (pintype "passive"))
      (node (ref "U1") (pin "5") (pinfunction "DI(IO0)_5") (pintype "bidirectional"))
      (node (ref "U2") (pin "7") (pinfunction "IO7_7") (pintype "bidirectional"))
    )
    (net (code "21") (name "Net-(CHG_LED-PadC)") (class "Default")
      (node (ref "CHG_LED") (pin "C") (pinfunction "C_C") (pintype "passive"))
      (node (ref "R1-BAT") (pin "1") (pinfunction "1_1") (pintype "passive"))
    )
    (net (code "22") (name "Net-(D2-CATHODE)") (class "Default")
      (node (ref "C1_BAT1") (pin "1") (pinfunction "1_1") (pintype "passive"))
      (node (ref "D2") (pin "1") (pinfunction "CATHODE_1") (pintype "bidirectional"))
      (node (ref "IC4") (pin "1") (pinfunction "VIN_1") (pintype "bidirectional"))
      (node (ref "IC4") (pin "3") (pinfunction "CE_3") (pintype "bidirectional"))
      (node (ref "Q1") (pin "2") (pinfunction "S_2") (pintype "bidirectional"))
    )
    (net (code "23") (name "Net-(D3-A)") (class "Default")
      (node (ref "C4") (pin "1") (pinfunction "1_1") (pintype "passive"))
      (node (ref "D3") (pin "2") (pinfunction "A_2") (pintype "bidirectional"))
      (node (ref "D4") (pin "1") (pinfunction "K_1") (pintype "bidirectional"))
    )
    (net (code "24") (name "Net-(D7-CATHODE)") (class "Default")
      (node (ref "D7") (pin "1") (pinfunction "CATHODE_1") (pintype "bidirectional"))
      (node (ref "R_CAPACITOR") (pin "1") (pinfunction "1_1") (pintype "passive"))
    )
    (net (code "25") (name "Net-(D10-Pad2)") (class "Default")
      (node (ref "D10") (pin "2") (pinfunction "2_2") (pintype "passive"))
      (node (ref "D11") (pin "2") (pinfunction "2_2") (pintype "passive"))
      (node (ref "D12") (pin "2") (pinfunction "2_2") (pintype "passive"))
      (node (ref "D6") (pin "2") (pinfunction "2_2") (pintype "passive"))
      (node (ref "D8") (pin "2") (pinfunction "2_2") (pintype "passive"))
      (node (ref "D9") (pin "2") (pinfunction "2_2") (pintype "passive"))
    )
    (net (code "26") (name "Net-(EPD_C1-Pad1)") (class "Default")
      (node (ref "EPD_C1") (pin "1") (pinfunction "1_1") (pintype "passive"))
      (node (ref "J1") (pin "4") (pinfunction "4_4") (pintype "bidirectional"))
    )
    (net (code "27") (name "Net-(EPD_C2-Pad1)") (class "Default")
      (node (ref "EPD_C2") (pin "1") (pinfunction "1_1") (pintype "passive"))
      (node (ref "J1") (pin "5") (pinfunction "5_5") (pintype "bidirectional"))
    )
    (net (code "28") (name "Net-(EPD_C6-Pad1)") (class "Default")
      (node (ref "EPD_C6") (pin "1") (pinfunction "1_1") (pintype "passive"))
      (node (ref "J1") (pin "18") (pinfunction "18_18") (pintype "bidirectional"))
    )
    (net (code "29") (name "Net-(EPD_C7-Pad1)") (class "Default")
      (node (ref "EPD_C7") (pin "1") (pinfunction "1_1") (pintype "passive"))
      (node (ref "J1") (pin "19") (pinfunction "19_19") (pintype "bidirectional"))
    )
    (net (code "30") (name "Net-(EPD_C8-Pad1)") (class "Default")
      (node (ref "EPD_C8") (pin "1") (pinfunction "1_1") (pintype "passive"))
      (node (ref "J1") (pin "20") (pinfunction "20_20") (pintype "bidirectional"))
    )
    (net (code "31") (name "Net-(EPD_C10-Pad1)") (class "Default")
      (node (ref "EPD_C10") (pin "1") (pinfunction "1_1") (pintype "passive"))
      (node (ref "J1") (pin "22") (pinfunction "22_22") (pintype "bidirectional"))
    )
    (net (code "32") (name "Net-(EPD_C12-Pad1)") (class "Default")
      (node (ref "EPD_C12") (pin "1") (pinfunction "1_1") (pintype "passive"))
      (node (ref "J1") (pin "24") (pinfunction "24_24") (pintype "bidirectional"))
    )
    (net (code "33") (name "Net-(IC1-CT)") (class "Default")
      (node (ref "C_DELAY") (pin "1") (pinfunction "1_1") (pintype "passive"))
      (node (ref "IC1") (pin "5") (pinfunction "CT_5") (pintype "bidirectional"))
    )
    (net (code "34") (name "Net-(J2-PadA5)") (class "Default")
      (node (ref "J2") (pin "A5") (pinfunction "A5_A5") (pintype "bidirectional"))
      (node (ref "R2-USB1") (pin "2") (pinfunction "2_2") (pintype "passive"))
    )
    (net (code "35") (name "Net-(J2-PadB5)") (class "Default")
      (node (ref "J2") (pin "B5") (pinfunction "B5_B5") (pintype "bidirectional"))
      (node (ref "R2-USB") (pin "1") (pinfunction "1_1") (pintype "passive"))
    )
    (net (code "36") (name "Net-(MCP73831-PROG)") (class "Default")
      (node (ref "MCP73831") (pin "5") (pinfunction "PROG_5") (pintype "input"))
      (node (ref "R2_BAT") (pin "2") (pinfunction "2_2") (pintype "passive"))
    )
    (net (code "37") (name "Net-(MCP73831-STAT)") (class "Default")
      (node (ref "MCP73831") (pin "1") (pinfunction "STAT_1") (pintype "output"))
      (node (ref "R1-BAT") (pin "2") (pinfunction "2_2") (pintype "passive"))
    )
    (net (code "38") (name "PREVGH") (class "Default")
      (node (ref "D5") (pin "1") (pinfunction "K_1") (pintype "bidirectional"))
      (node (ref "EPD_C9") (pin "1") (pinfunction "1_1") (pintype "passive"))
      (node (ref "J1") (pin "21") (pinfunction "21_21") (pintype "bidirectional"))
    )
    (net (code "39") (name "PREVGL") (class "Default")
      (node (ref "D4") (pin "2") (pinfunction "A_2") (pintype "bidirectional"))
      (node (ref "EPD_C11") (pin "1") (pinfunction "1_1") (pintype "passive"))
      (node (ref "J1") (pin "23") (pinfunction "23_23") (pintype "bidirectional"))
    )
    (net (code "40") (name "RESE") (class "Default")
      (node (ref "J1") (pin "3") (pinfunction "3_3") (pintype "bidirectional"))
      (node (ref "Q3") (pin "2") (pinfunction "S_2") (pintype "bidirectional"))
      (node (ref "R3") (pin "2") (pinfunction "2_2") (pintype "passive"))
    )
    (net (code "41") (name "RESE'") (class "Default")
      (node (ref "R2") (pin "2") (pinfunction "2_2") (pintype "passive"))
      (node (ref "R3") (pin "1") (pinfunction "1_1") (pintype "passive"))
      (node (ref "SJ1") (pin "2") (pinfunction "2_2") (pintype "passive"))
    )
    (net (code "42") (name "RESET") (class "Default")
      (node (ref "C5") (pin "1") (pinfunction "1_1") (pintype "passive"))
      (node (ref "IC1") (pin "1") (pinfunction "VOUT_1") (pintype "bidirectional"))
      (node (ref "RESET_BUTTON") (pin "3") (pinfunction "3_3") (pintype "passive"))
      (node (ref "RESET_BUTTON") (pin "4") (pinfunction "4_4") (pintype "passive"))
      (node (ref "R_RESET") (pin "2") (pinfunction "2_2") (pintype "passive"))
      (node (ref "U2") (pin "3") (pinfunction "EN_3") (pintype "input"))
    )
    (net (code "43") (name "RTC_RST") (class "Default")
      (node (ref "U2") (pin "16") (pinfunction "IO18_16") (pintype "bidirectional"))
      (node (ref "U3") (pin "4") (pinfunction "~{RST}_4") (pintype "input"))
    )
    (net (code "44") (name "RX") (class "Default")
      (node (ref "RX") (pin "TP") (pinfunction "TP_TP") (pintype "input"))
      (node (ref "U2") (pin "24") (pinfunction "RXD0/GPIO17_24") (pintype "bidirectional"))
    )
    (net (code "45") (name "SCK") (class "Default")
      (node (ref "D8") (pin "1") (pinfunction "1_1") (pintype "passive"))
      (node (ref "J1") (pin "13") (pinfunction "13_13") (pintype "bidirectional"))
      (node (ref "J4") (pin "P5") (pinfunction "CLK_P5") (pintype "bidirectional"))
      (node (ref "R6") (pin "1") (pinfunction "1_1") (pintype "passive"))
      (node (ref "SCK") (pin "TP") (pinfunction "TP_TP") (pintype "input"))
      (node (ref "U1") (pin "6") (pinfunction "CLK_6") (pintype "input"))
      (node (ref "U2") (pin "6") (pinfunction "IO6_6") (pintype "bidirectional"))
    )
    (net (code "46") (name "SCL") (class "Default")
      (node (ref "J3") (pin "4") (pinfunction "4_4") (pintype "passive"))
      (node (ref "R2_PINH") (pin "1") (pinfunction "1_1") (pintype "passive"))
      (node (ref "SENSOR2") (pin "4") (pinfunction "SCK_4") (pintype "input"))
      (node (ref "U2") (pin "20") (pinfunction "IO22_20") (pintype "bidirectional"))
      (node (ref "U3") (pin "16") (pinfunction "SCL_16") (pintype "input"))
      (node (ref "U4") (pin "7") (pinfunction "SCL_7") (pintype "input"))
    )
    (net (code "47") (name "SDA") (class "Default")
      (node (ref "J3") (pin "3") (pinfunction "3_3") (pintype "passive"))
      (node (ref "R1_PINH") (pin "1") (pinfunction "1_1") (pintype "passive"))
      (node (ref "SENSOR2") (pin "3") (pinfunction "SDI_3") (pintype "bidirectional"))
      (node (ref "U2") (pin "19") (pinfunction "IO21_19") (pintype "bidirectional"))
      (node (ref "U3") (pin "15") (pinfunction "SDA_15") (pintype "bidirectional"))
      (node (ref "U4") (pin "8") (pinfunction "SDA_8") (pintype "bidirectional"))
    )
    (net (code "48") (name "SRC") (class "Default")
      (node (ref "C4") (pin "2") (pinfunction "2_2") (pintype "passive"))
      (node (ref "D5") (pin "2") (pinfunction "A_2") (pintype "bidirectional"))
      (node (ref "L1") (pin "1") (pinfunction "1_1") (pintype "passive"))
      (node (ref "Q3") (pin "3") (pinfunction "D_3") (pintype "bidirectional"))
    )
    (net (code "49") (name "SS_SD") (class "Default")
      (node (ref "D11") (pin "1") (pinfunction "1_1") (pintype "passive"))
      (node (ref "J4") (pin "P2") (pinfunction "CD/DAT3_P2") (pintype "bidirectional"))
      (node (ref "R10") (pin "1") (pinfunction "1_1") (pintype "passive"))
      (node (ref "U2") (pin "4") (pinfunction "IO4_4") (pintype "bidirectional"))
    )
    (net (code "50") (name "TX") (class "Default")
      (node (ref "TX") (pin "TP") (pinfunction "TP_TP") (pintype "input"))
      (node (ref "U2") (pin "25") (pinfunction "TXD0/GPIO16_25") (pintype "bidirectional"))
    )
    (net (code "51") (name "USB_D+") (class "Default")
      (node (ref "D1") (pin "1") (pinfunction "I/O1_1_1") (pintype "bidirectional"))
      (node (ref "U2") (pin "14") (pinfunction "IO13_14") (pintype "bidirectional"))
    )
    (net (code "52") (name "USB_D-") (class "Default")
      (node (ref "D1") (pin "3") (pinfunction "I/O2_1_3") (pintype "bidirectional"))
      (node (ref "U2") (pin "13") (pinfunction "IO12_13") (pintype "bidirectional"))
    )
    (net (code "53") (name "VBAT") (class "Default")
      (node (ref "C2_BAT") (pin "1") (pinfunction "1_1") (pintype "passive"))
      (node (ref "MCP73831") (pin "3") (pinfunction "VBAT_3") (pintype "power_in"))
      (node (ref "Q1") (pin "3") (pinfunction "D_3") (pintype "bidirectional"))
      (node (ref "U4") (pin "2") (pinfunction "CELL_2") (pintype "power_in"))
      (node (ref "U4") (pin "3") (pinfunction "VDD_3") (pintype "power_in"))
      (node (ref "VBAT") (pin "TP") (pinfunction "TP_TP") (pintype "input"))
    )
    (net (code "54") (name "VBUS") (class "Default")
      (node (ref "C1_BAT") (pin "1") (pinfunction "1_1") (pintype "passive"))
      (node (ref "C4_USB") (pin "1") (pinfunction "1_1") (pintype "passive"))
      (node (ref "C5_USB") (pin "1") (pinfunction "1_1") (pintype "passive"))
      (node (ref "CHG_LED") (pin "A") (pinfunction "A_A") (pintype "passive"))
      (node (ref "D1") (pin "5") (pinfunction "VBUS_5") (pintype "bidirectional"))
      (node (ref "D2") (pin "2") (pinfunction "ANODE_2") (pintype "bidirectional"))
      (node (ref "MCP73831") (pin "4") (pinfunction "VIN_4") (pintype "power_in"))
      (node (ref "PFMF.050.1") (pin "2") (pinfunction "2_2") (pintype "passive"))
      (node (ref "Q1") (pin "1") (pinfunction "G_1") (pintype "bidirectional"))
      (node (ref "R1_PWRUSB") (pin "2") (pinfunction "2_2") (pintype "passive"))
      (node (ref "VBUS") (pin "TP") (pinfunction "TP_TP") (pintype "input"))
    )
    (net (code "55") (name "VRTC") (class "Default")
      (node (ref "C10_SUPERCAP") (pin "2") (pinfunction "2_2") (pintype "passive"))
      (node (ref "C8") (pin "1") (pinfunction "1_1") (pintype "passive"))
      (node (ref "R_CAPACITOR") (pin "2") (pinfunction "2_2") (pintype "passive"))
      (node (ref "U3") (pin "14") (pinfunction "VBAT_14") (pintype "power_in"))
    )
    (net (code "56") (name "VUSB") (class "Default")
      (node (ref "J2") (pin "A4") (pinfunction "A4_A4") (pintype "bidirectional"))
      (node (ref "J2") (pin "A9") (pinfunction "A9_A9") (pintype "bidirectional"))
      (node (ref "J2") (pin "B4") (pinfunction "B4_B4") (pintype "bidirectional"))
      (node (ref "J2") (pin "B9") (pinfunction "B9_B9") (pintype "bidirectional"))
      (node (ref "PFMF.050.1") (pin "1") (pinfunction "1_1") (pintype "passive"))
    )
    (net (code "57") (name "unconnected-(IC1-NC-Pad4)") (class "Default")
      (node (ref "IC1") (pin "4") (pinfunction "NC_4") (pintype "no_connect"))
    )
    (net (code "58") (name "unconnected-(IC4-NC-Pad4)") (class "Default")
      (node (ref "IC4") (pin "4") (pinfunction "NC_4") (pintype "no_connect"))
    )
    (net (code "59") (name "unconnected-(J1-Pad1)") (class "Default")
      (node (ref "J1") (pin "1") (pinfunction "1_1") (pintype "bidirectional"))
    )
    (net (code "60") (name "unconnected-(J1-Pad6)") (class "Default")
      (node (ref "J1") (pin "6") (pinfunction "6_6") (pintype "bidirectional"))
    )
    (net (code "61") (name "unconnected-(J1-Pad7)") (class "Default")
      (node (ref "J1") (pin "7") (pinfunction "7_7") (pintype "bidirectional"))
    )
    (net (code "62") (name "unconnected-(J2-PadA8)") (class "Default")
      (node (ref "J2") (pin "A8") (pinfunction "A8_A8") (pintype "bidirectional"))
    )
    (net (code "63") (name "unconnected-(J2-PadB8)") (class "Default")
      (node (ref "J2") (pin "B8") (pinfunction "B8_B8") (pintype "bidirectional"))
    )
    (net (code "64") (name "unconnected-(J4-DAT1-PadP8)") (class "Default")
      (node (ref "J4") (pin "P8") (pinfunction "DAT1_P8") (pintype "bidirectional"))
    )
    (net (code "65") (name "unconnected-(J4-DAT2-PadP1)") (class "Default")
      (node (ref "J4") (pin "P1") (pinfunction "DAT2_P1") (pintype "bidirectional"))
    )
    (net (code "66") (name "unconnected-(J4-DETECTION_1-PadS1)") (class "Default")
      (node (ref "J4") (pin "S1") (pinfunction "DETECTION_1_S1") (pintype "bidirectional"))
    )
    (net (code "67") (name "unconnected-(J4-DETECTION_2-PadS2)") (class "Default")
      (node (ref "J4") (pin "S2") (pinfunction "DETECTION_2_S2") (pintype "bidirectional"))
    )
    (net (code "68") (name "unconnected-(U2-NC-Pad22)") (class "Default")
      (node (ref "U2") (pin "22") (pinfunction "NC_22") (pintype "no_connect"))
    )
    (net (code "69") (name "unconnected-(U4-~{ALERT}-Pad5)") (class "Default")
      (node (ref "U4") (pin "5") (pinfunction "~{ALERT}_5") (pintype "output"))
    )
  )
)
